# ringmod_osc.net
KiCad netlist of a schematic drawn in EAGLE
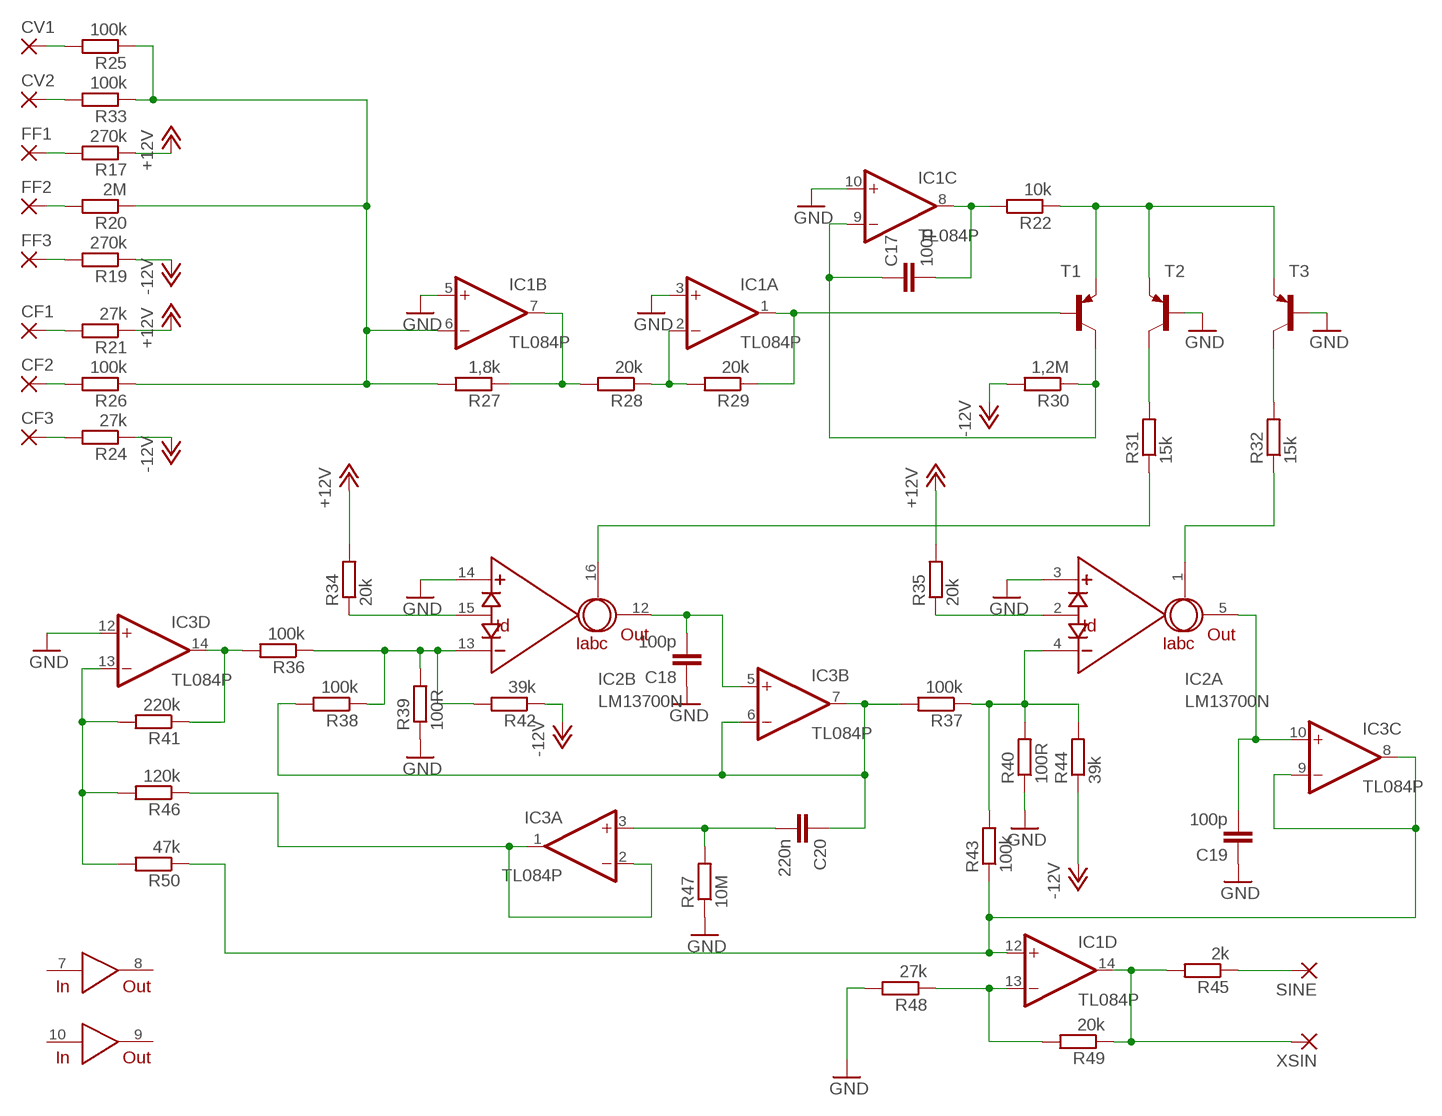
[diagram p0: schematic, sheet 1]
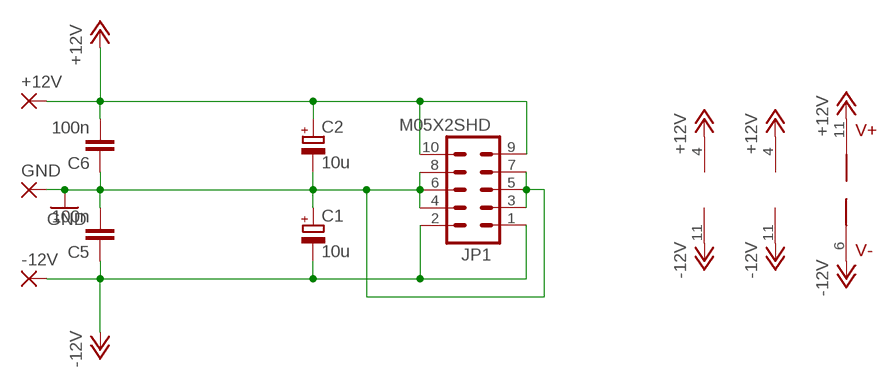
[diagram p1: schematic, sheet 2]

(export (version "E")
  (design (tool "Eeschema 10.0.6"))
  (components
    (comp (ref "+12V")
      (value "2,54/1,0")
      (footprint "eagle-import:2,54_1,0")
      (libsource (lib "eagle-import") (part "2,54/1,0"))
    )
    (comp (ref "-12V")
      (value "2,54/1,0")
      (footprint "eagle-import:2,54_1,0")
      (libsource (lib "eagle-import") (part "2,54/1,0"))
    )
    (comp (ref "C1")
      (value "10u")
      (footprint "eagle-import:E3,5-8")
      (libsource (lib "eagle-import") (part "CPOL-EUE3.5-8"))
    )
    (comp (ref "C2")
      (value "10u")
      (footprint "eagle-import:E3,5-8")
      (libsource (lib "eagle-import") (part "CPOL-EUE3.5-8"))
    )
    (comp (ref "C5")
      (value "100n")
      (footprint "eagle-import:C050-035X075")
      (libsource (lib "eagle-import") (part "C-EU050-035X075"))
    )
    (comp (ref "C6")
      (value "100n")
      (footprint "eagle-import:C050-035X075")
      (libsource (lib "eagle-import") (part "C-EU050-035X075"))
    )
    (comp (ref "GND")
      (value "2,54/1,0")
      (footprint "eagle-import:2,54_1,0")
      (libsource (lib "eagle-import") (part "2,54/1,0"))
    )
    (comp (ref "IC1")
      (value "TL084P")
      (footprint "eagle-import:DIL14")
      (libsource (lib "eagle-import") (part "TL084P"))
    )
    (comp (ref "IC2")
      (value "LM13700N")
      (footprint "eagle-import:DIL16")
      (libsource (lib "eagle-import") (part "LM13700N"))
    )
    (comp (ref "IC3")
      (value "TL084P")
      (footprint "eagle-import:DIL14")
      (libsource (lib "eagle-import") (part "TL084P"))
    )
    (comp (ref "JP1")
      (value "M05X2SHD")
      (footprint "eagle-import:2X5-SHROUDED")
      (libsource (lib "eagle-import") (part "M05X2SHD"))
    )
    (comp (ref "C17")
      (value "100p")
      (footprint "eagle-import:C050-035X075")
      (libsource (lib "eagle-import") (part "C-EU050-035X075"))
    )
    (comp (ref "C18")
      (value "100p")
      (footprint "eagle-import:C050-035X075")
      (libsource (lib "eagle-import") (part "C-EU050-035X075"))
    )
    (comp (ref "C19")
      (value "100p")
      (footprint "eagle-import:C050-035X075")
      (libsource (lib "eagle-import") (part "C-EU050-035X075"))
    )
    (comp (ref "C20")
      (value "220n")
      (footprint "eagle-import:C050-035X075")
      (libsource (lib "eagle-import") (part "C-EU050-035X075"))
    )
    (comp (ref "CF1")
      (value "2,54/1,0")
      (footprint "eagle-import:2,54_1,0")
      (libsource (lib "eagle-import") (part "2,54/1,0"))
    )
    (comp (ref "CF2")
      (value "2,54/1,0")
      (footprint "eagle-import:2,54_1,0")
      (libsource (lib "eagle-import") (part "2,54/1,0"))
    )
    (comp (ref "CF3")
      (value "2,54/1,0")
      (footprint "eagle-import:2,54_1,0")
      (libsource (lib "eagle-import") (part "2,54/1,0"))
    )
    (comp (ref "CV1")
      (value "2,54/1,0")
      (footprint "eagle-import:2,54_1,0")
      (libsource (lib "eagle-import") (part "2,54/1,0"))
    )
    (comp (ref "CV2")
      (value "2,54/1,0")
      (footprint "eagle-import:2,54_1,0")
      (libsource (lib "eagle-import") (part "2,54/1,0"))
    )
    (comp (ref "FF1")
      (value "2,54/1,0")
      (footprint "eagle-import:2,54_1,0")
      (libsource (lib "eagle-import") (part "2,54/1,0"))
    )
    (comp (ref "FF2")
      (value "2,54/1,0")
      (footprint "eagle-import:2,54_1,0")
      (libsource (lib "eagle-import") (part "2,54/1,0"))
    )
    (comp (ref "FF3")
      (value "2,54/1,0")
      (footprint "eagle-import:2,54_1,0")
      (libsource (lib "eagle-import") (part "2,54/1,0"))
    )
    (comp (ref "R17")
      (value "270k")
      (footprint "eagle-import:0309V")
      (libsource (lib "eagle-import") (part "R-EU_0309/V"))
    )
    (comp (ref "R19")
      (value "270k")
      (footprint "eagle-import:0309V")
      (libsource (lib "eagle-import") (part "R-EU_0309/V"))
    )
    (comp (ref "R20")
      (value "2M")
      (footprint "eagle-import:0309V")
      (libsource (lib "eagle-import") (part "R-EU_0309/V"))
    )
    (comp (ref "R21")
      (value "27k")
      (footprint "eagle-import:0309V")
      (libsource (lib "eagle-import") (part "R-EU_0309/V"))
    )
    (comp (ref "R22")
      (value "10k")
      (footprint "eagle-import:0309_10")
      (libsource (lib "eagle-import") (part "R-EU_0309/10"))
    )
    (comp (ref "R24")
      (value "27k")
      (footprint "eagle-import:0309V")
      (libsource (lib "eagle-import") (part "R-EU_0309/V"))
    )
    (comp (ref "R25")
      (value "100k")
      (footprint "eagle-import:0309V")
      (libsource (lib "eagle-import") (part "R-EU_0309/V"))
    )
    (comp (ref "R26")
      (value "100k")
      (footprint "eagle-import:0309V")
      (libsource (lib "eagle-import") (part "R-EU_0309/V"))
    )
    (comp (ref "R27")
      (value "1,8k")
      (footprint "eagle-import:0309_10")
      (libsource (lib "eagle-import") (part "R-EU_0309/10"))
    )
    (comp (ref "R28")
      (value "20k")
      (footprint "eagle-import:0309_10")
      (libsource (lib "eagle-import") (part "R-EU_0309/10"))
    )
    (comp (ref "R29")
      (value "20k")
      (footprint "eagle-import:0309_10")
      (libsource (lib "eagle-import") (part "R-EU_0309/10"))
    )
    (comp (ref "R30")
      (value "1,2M")
      (footprint "eagle-import:0309_10")
      (libsource (lib "eagle-import") (part "R-EU_0309/10"))
    )
    (comp (ref "R31")
      (value "15k")
      (footprint "eagle-import:0309_10")
      (libsource (lib "eagle-import") (part "R-EU_0309/10"))
    )
    (comp (ref "R32")
      (value "15k")
      (footprint "eagle-import:0309_10")
      (libsource (lib "eagle-import") (part "R-EU_0309/10"))
    )
    (comp (ref "R33")
      (value "100k")
      (footprint "eagle-import:0309V")
      (libsource (lib "eagle-import") (part "R-EU_0309/V"))
    )
    (comp (ref "R34")
      (value "20k")
      (footprint "eagle-import:0309_10")
      (libsource (lib "eagle-import") (part "R-EU_0309/10"))
    )
    (comp (ref "R35")
      (value "20k")
      (footprint "eagle-import:0309_10")
      (libsource (lib "eagle-import") (part "R-EU_0309/10"))
    )
    (comp (ref "R36")
      (value "100k")
      (footprint "eagle-import:0309_10")
      (libsource (lib "eagle-import") (part "R-EU_0309/10"))
    )
    (comp (ref "R37")
      (value "100k")
      (footprint "eagle-import:0309_10")
      (libsource (lib "eagle-import") (part "R-EU_0309/10"))
    )
    (comp (ref "R38")
      (value "100k")
      (footprint "eagle-import:0309_10")
      (libsource (lib "eagle-import") (part "R-EU_0309/10"))
    )
    (comp (ref "R39")
      (value "100R")
      (footprint "eagle-import:0309_10")
      (libsource (lib "eagle-import") (part "R-EU_0309/10"))
    )
    (comp (ref "R40")
      (value "100R")
      (footprint "eagle-import:0309_10")
      (libsource (lib "eagle-import") (part "R-EU_0309/10"))
    )
    (comp (ref "R41")
      (value "220k")
      (footprint "eagle-import:0309_10")
      (libsource (lib "eagle-import") (part "R-EU_0309/10"))
    )
    (comp (ref "R42")
      (value "39k")
      (footprint "eagle-import:0309_10")
      (libsource (lib "eagle-import") (part "R-EU_0309/10"))
    )
    (comp (ref "R43")
      (value "100k")
      (footprint "eagle-import:0309_10")
      (libsource (lib "eagle-import") (part "R-EU_0309/10"))
    )
    (comp (ref "R44")
      (value "39k")
      (footprint "eagle-import:0309_10")
      (libsource (lib "eagle-import") (part "R-EU_0309/10"))
    )
    (comp (ref "R45")
      (value "2k")
      (footprint "eagle-import:0309_10")
      (libsource (lib "eagle-import") (part "R-EU_0309/10"))
    )
    (comp (ref "R46")
      (value "120k")
      (footprint "eagle-import:0309_10")
      (libsource (lib "eagle-import") (part "R-EU_0309/10"))
    )
    (comp (ref "R47")
      (value "10M")
      (footprint "eagle-import:0309_10")
      (libsource (lib "eagle-import") (part "R-EU_0309/10"))
    )
    (comp (ref "R48")
      (value "27k")
      (footprint "eagle-import:0309_10")
      (libsource (lib "eagle-import") (part "R-EU_0309/10"))
    )
    (comp (ref "R49")
      (value "20k")
      (footprint "eagle-import:0309_10")
      (libsource (lib "eagle-import") (part "R-EU_0309/10"))
    )
    (comp (ref "R50")
      (value "47k")
      (footprint "eagle-import:0309_10")
      (libsource (lib "eagle-import") (part "R-EU_0309/10"))
    )
    (comp (ref "SINE")
      (value "2,54/1,0")
      (footprint "eagle-import:2,54_1,0")
      (libsource (lib "eagle-import") (part "2,54/1,0"))
    )
    (comp (ref "T1")
      (value "2N3906-PNP-TO92-EBC")
      (footprint "eagle-import:TO92-EBC")
      (libsource (lib "eagle-import") (part "-PNP-TO92-EBC2N3906"))
    )
    (comp (ref "T2")
      (value "2N3906-PNP-TO92-EBC")
      (footprint "eagle-import:TO92-EBC")
      (libsource (lib "eagle-import") (part "-PNP-TO92-EBC2N3906"))
    )
    (comp (ref "T3")
      (value "2N3906-PNP-TO92-EBC")
      (footprint "eagle-import:TO92-EBC")
      (libsource (lib "eagle-import") (part "-PNP-TO92-EBC2N3906"))
    )
    (comp (ref "XSIN")
      (value "2,54/1,0")
      (footprint "eagle-import:2,54_1,0")
      (libsource (lib "eagle-import") (part "2,54/1,0"))
    )
  )
  (nets
    (net (code "1") (name "+12V") (class "Default")
      (node (ref "+12V") (pin "1") (pinfunction "P_1") (pintype "passive"))
      (node (ref "C2") (pin "+") (pinfunction "+_+") (pintype "passive"))
      (node (ref "C6") (pin "2") (pinfunction "2_2") (pintype "passive"))
      (node (ref "IC1") (pin "4") (pinfunction "V+_4") (pintype "power_in"))
      (node (ref "IC2") (pin "11") (pinfunction "V+_11") (pintype "bidirectional"))
      (node (ref "IC3") (pin "4") (pinfunction "V+_4") (pintype "power_in"))
      (node (ref "JP1") (pin "10") (pinfunction "10_10") (pintype "passive"))
      (node (ref "JP1") (pin "9") (pinfunction "9_9") (pintype "passive"))
      (node (ref "R17") (pin "1") (pinfunction "1_1") (pintype "passive"))
      (node (ref "R21") (pin "1") (pinfunction "1_1") (pintype "passive"))
      (node (ref "R34") (pin "2") (pinfunction "2_2") (pintype "passive"))
      (node (ref "R35") (pin "2") (pinfunction "2_2") (pintype "passive"))
    )
    (net (code "2") (name "-12V") (class "Default")
      (node (ref "-12V") (pin "1") (pinfunction "P_1") (pintype "passive"))
      (node (ref "C1") (pin "-") (pinfunction "-_-") (pintype "passive"))
      (node (ref "C5") (pin "1") (pinfunction "1_1") (pintype "passive"))
      (node (ref "IC1") (pin "11") (pinfunction "V-_11") (pintype "power_in"))
      (node (ref "IC2") (pin "6") (pinfunction "V-_6") (pintype "bidirectional"))
      (node (ref "IC3") (pin "11") (pinfunction "V-_11") (pintype "power_in"))
      (node (ref "JP1") (pin "1") (pinfunction "1_1") (pintype "passive"))
      (node (ref "JP1") (pin "2") (pinfunction "2_2") (pintype "passive"))
      (node (ref "R19") (pin "1") (pinfunction "1_1") (pintype "passive"))
      (node (ref "R24") (pin "1") (pinfunction "1_1") (pintype "passive"))
      (node (ref "R30") (pin "2") (pinfunction "2_2") (pintype "passive"))
      (node (ref "R42") (pin "1") (pinfunction "1_1") (pintype "passive"))
      (node (ref "R44") (pin "1") (pinfunction "1_1") (pintype "passive"))
    )
    (net (code "3") (name "GND") (class "Default")
      (node (ref "C1") (pin "+") (pinfunction "+_+") (pintype "passive"))
      (node (ref "C18") (pin "1") (pinfunction "1_1") (pintype "passive"))
      (node (ref "C19") (pin "1") (pinfunction "1_1") (pintype "passive"))
      (node (ref "C2") (pin "-") (pinfunction "-_-") (pintype "passive"))
      (node (ref "C5") (pin "2") (pinfunction "2_2") (pintype "passive"))
      (node (ref "C6") (pin "1") (pinfunction "1_1") (pintype "passive"))
      (node (ref "GND") (pin "1") (pinfunction "P_1") (pintype "passive"))
      (node (ref "IC1") (pin "10") (pinfunction "+IN_10") (pintype "input"))
      (node (ref "IC1") (pin "3") (pinfunction "+IN_3") (pintype "input"))
      (node (ref "IC1") (pin "5") (pinfunction "+IN_5") (pintype "input"))
      (node (ref "IC2") (pin "14") (pinfunction "+IN_14") (pintype "bidirectional"))
      (node (ref "IC2") (pin "3") (pinfunction "+IN_3") (pintype "bidirectional"))
      (node (ref "IC3") (pin "12") (pinfunction "+IN_12") (pintype "input"))
      (node (ref "JP1") (pin "3") (pinfunction "3_3") (pintype "passive"))
      (node (ref "JP1") (pin "4") (pinfunction "4_4") (pintype "passive"))
      (node (ref "JP1") (pin "5") (pinfunction "5_5") (pintype "passive"))
      (node (ref "JP1") (pin "6") (pinfunction "6_6") (pintype "passive"))
      (node (ref "JP1") (pin "7") (pinfunction "7_7") (pintype "passive"))
      (node (ref "JP1") (pin "8") (pinfunction "8_8") (pintype "passive"))
      (node (ref "R39") (pin "1") (pinfunction "1_1") (pintype "passive"))
      (node (ref "R40") (pin "1") (pinfunction "1_1") (pintype "passive"))
      (node (ref "R47") (pin "1") (pinfunction "1_1") (pintype "passive"))
      (node (ref "R48") (pin "2") (pinfunction "2_2") (pintype "passive"))
      (node (ref "T2") (pin "B") (pinfunction "B_B") (pintype "passive"))
      (node (ref "T3") (pin "B") (pinfunction "B_B") (pintype "passive"))
    )
    (net (code "4") (name "Net-(CF1-P)") (class "Default")
      (node (ref "CF1") (pin "1") (pinfunction "P_1") (pintype "passive"))
      (node (ref "R21") (pin "2") (pinfunction "2_2") (pintype "passive"))
    )
    (net (code "5") (name "Net-(CF2-P)") (class "Default")
      (node (ref "CF2") (pin "1") (pinfunction "P_1") (pintype "passive"))
      (node (ref "R26") (pin "2") (pinfunction "2_2") (pintype "passive"))
    )
    (net (code "6") (name "Net-(CF3-P)") (class "Default")
      (node (ref "CF3") (pin "1") (pinfunction "P_1") (pintype "passive"))
      (node (ref "R24") (pin "2") (pinfunction "2_2") (pintype "passive"))
    )
    (net (code "7") (name "Net-(CV1-P)") (class "Default")
      (node (ref "CV1") (pin "1") (pinfunction "P_1") (pintype "passive"))
      (node (ref "R25") (pin "2") (pinfunction "2_2") (pintype "passive"))
    )
    (net (code "8") (name "Net-(CV2-P)") (class "Default")
      (node (ref "CV2") (pin "1") (pinfunction "P_1") (pintype "passive"))
      (node (ref "R33") (pin "2") (pinfunction "2_2") (pintype "passive"))
    )
    (net (code "9") (name "Net-(FF1-P)") (class "Default")
      (node (ref "FF1") (pin "1") (pinfunction "P_1") (pintype "passive"))
      (node (ref "R17") (pin "2") (pinfunction "2_2") (pintype "passive"))
    )
    (net (code "10") (name "Net-(FF2-P)") (class "Default")
      (node (ref "FF2") (pin "1") (pinfunction "P_1") (pintype "passive"))
      (node (ref "R20") (pin "2") (pinfunction "2_2") (pintype "passive"))
    )
    (net (code "11") (name "Net-(FF3-P)") (class "Default")
      (node (ref "FF3") (pin "1") (pinfunction "P_1") (pintype "passive"))
      (node (ref "R19") (pin "2") (pinfunction "2_2") (pintype "passive"))
    )
    (net (code "12") (name "Net-(IC1A--IN)") (class "Default")
      (node (ref "IC1") (pin "2") (pinfunction "-IN_2") (pintype "input"))
      (node (ref "R28") (pin "1") (pinfunction "1_1") (pintype "passive"))
      (node (ref "R29") (pin "2") (pinfunction "2_2") (pintype "passive"))
    )
    (net (code "13") (name "Net-(IC1A-OUT)") (class "Default")
      (node (ref "IC1") (pin "1") (pinfunction "OUT_1") (pintype "output"))
      (node (ref "R29") (pin "1") (pinfunction "1_1") (pintype "passive"))
      (node (ref "T1") (pin "B") (pinfunction "B_B") (pintype "passive"))
    )
    (net (code "14") (name "Net-(IC1B--IN)") (class "Default")
      (node (ref "IC1") (pin "6") (pinfunction "-IN_6") (pintype "input"))
      (node (ref "R20") (pin "1") (pinfunction "1_1") (pintype "passive"))
      (node (ref "R25") (pin "1") (pinfunction "1_1") (pintype "passive"))
      (node (ref "R26") (pin "1") (pinfunction "1_1") (pintype "passive"))
      (node (ref "R27") (pin "2") (pinfunction "2_2") (pintype "passive"))
      (node (ref "R33") (pin "1") (pinfunction "1_1") (pintype "passive"))
    )
    (net (code "15") (name "Net-(IC1B-OUT)") (class "Default")
      (node (ref "IC1") (pin "7") (pinfunction "OUT_7") (pintype "output"))
      (node (ref "R27") (pin "1") (pinfunction "1_1") (pintype "passive"))
      (node (ref "R28") (pin "2") (pinfunction "2_2") (pintype "passive"))
    )
    (net (code "16") (name "Net-(IC1C--IN)") (class "Default")
      (node (ref "C17") (pin "1") (pinfunction "1_1") (pintype "passive"))
      (node (ref "IC1") (pin "9") (pinfunction "-IN_9") (pintype "input"))
      (node (ref "R30") (pin "1") (pinfunction "1_1") (pintype "passive"))
      (node (ref "T1") (pin "C") (pinfunction "C_C") (pintype "passive"))
    )
    (net (code "17") (name "Net-(IC1C-OUT)") (class "Default")
      (node (ref "C17") (pin "2") (pinfunction "2_2") (pintype "passive"))
      (node (ref "IC1") (pin "8") (pinfunction "OUT_8") (pintype "output"))
      (node (ref "R22") (pin "2") (pinfunction "2_2") (pintype "passive"))
    )
    (net (code "18") (name "Net-(IC1D-+IN)") (class "Default")
      (node (ref "IC1") (pin "12") (pinfunction "+IN_12") (pintype "input"))
      (node (ref "IC3") (pin "8") (pinfunction "OUT_8") (pintype "output"))
      (node (ref "IC3") (pin "9") (pinfunction "-IN_9") (pintype "input"))
      (node (ref "R43") (pin "1") (pinfunction "1_1") (pintype "passive"))
      (node (ref "R50") (pin "1") (pinfunction "1_1") (pintype "passive"))
    )
    (net (code "19") (name "Net-(IC1D--IN)") (class "Default")
      (node (ref "IC1") (pin "13") (pinfunction "-IN_13") (pintype "input"))
      (node (ref "R48") (pin "1") (pinfunction "1_1") (pintype "passive"))
      (node (ref "R49") (pin "2") (pinfunction "2_2") (pintype "passive"))
    )
    (net (code "20") (name "Net-(IC1D-OUT)") (class "Default")
      (node (ref "IC1") (pin "14") (pinfunction "OUT_14") (pintype "output"))
      (node (ref "R45") (pin "2") (pinfunction "2_2") (pintype "passive"))
      (node (ref "R49") (pin "1") (pinfunction "1_1") (pintype "passive"))
      (node (ref "XSIN") (pin "1") (pinfunction "P_1") (pintype "passive"))
    )
    (net (code "21") (name "Net-(IC2A--IN)") (class "Default")
      (node (ref "IC2") (pin "4") (pinfunction "-IN_4") (pintype "bidirectional"))
      (node (ref "R37") (pin "1") (pinfunction "1_1") (pintype "passive"))
      (node (ref "R40") (pin "2") (pinfunction "2_2") (pintype "passive"))
      (node (ref "R43") (pin "2") (pinfunction "2_2") (pintype "passive"))
      (node (ref "R44") (pin "2") (pinfunction "2_2") (pintype "passive"))
    )
    (net (code "22") (name "Net-(IC2A-IABC)") (class "Default")
      (node (ref "IC2") (pin "1") (pinfunction "IABC_1") (pintype "bidirectional"))
      (node (ref "R32") (pin "1") (pinfunction "1_1") (pintype "passive"))
    )
    (net (code "23") (name "Net-(IC2A-ID)") (class "Default")
      (node (ref "IC2") (pin "2") (pinfunction "ID_2") (pintype "bidirectional"))
      (node (ref "R35") (pin "1") (pinfunction "1_1") (pintype "passive"))
    )
    (net (code "24") (name "Net-(IC2A-OUT)") (class "Default")
      (node (ref "C19") (pin "2") (pinfunction "2_2") (pintype "passive"))
      (node (ref "IC2") (pin "5") (pinfunction "OUT_5") (pintype "bidirectional"))
      (node (ref "IC3") (pin "10") (pinfunction "+IN_10") (pintype "input"))
    )
    (net (code "25") (name "Net-(IC2B--IN)") (class "Default")
      (node (ref "IC2") (pin "13") (pinfunction "-IN_13") (pintype "bidirectional"))
      (node (ref "R36") (pin "1") (pinfunction "1_1") (pintype "passive"))
      (node (ref "R38") (pin "1") (pinfunction "1_1") (pintype "passive"))
      (node (ref "R39") (pin "2") (pinfunction "2_2") (pintype "passive"))
      (node (ref "R42") (pin "2") (pinfunction "2_2") (pintype "passive"))
    )
    (net (code "26") (name "Net-(IC2B-IABC)") (class "Default")
      (node (ref "IC2") (pin "16") (pinfunction "IABC_16") (pintype "bidirectional"))
      (node (ref "R31") (pin "1") (pinfunction "1_1") (pintype "passive"))
    )
    (net (code "27") (name "Net-(IC2B-ID)") (class "Default")
      (node (ref "IC2") (pin "15") (pinfunction "ID_15") (pintype "bidirectional"))
      (node (ref "R34") (pin "1") (pinfunction "1_1") (pintype "passive"))
    )
    (net (code "28") (name "Net-(IC2B-OUT)") (class "Default")
      (node (ref "C18") (pin "2") (pinfunction "2_2") (pintype "passive"))
      (node (ref "IC2") (pin "12") (pinfunction "OUT_12") (pintype "bidirectional"))
      (node (ref "IC3") (pin "5") (pinfunction "+IN_5") (pintype "input"))
    )
    (net (code "29") (name "Net-(IC3A-+IN)") (class "Default")
      (node (ref "C20") (pin "2") (pinfunction "2_2") (pintype "passive"))
      (node (ref "IC3") (pin "3") (pinfunction "+IN_3") (pintype "input"))
      (node (ref "R47") (pin "2") (pinfunction "2_2") (pintype "passive"))
    )
    (net (code "30") (name "Net-(IC3A--IN)") (class "Default")
      (node (ref "IC3") (pin "1") (pinfunction "OUT_1") (pintype "output"))
      (node (ref "IC3") (pin "2") (pinfunction "-IN_2") (pintype "input"))
      (node (ref "R46") (pin "1") (pinfunction "1_1") (pintype "passive"))
    )
    (net (code "31") (name "Net-(IC3B--IN)") (class "Default")
      (node (ref "C20") (pin "1") (pinfunction "1_1") (pintype "passive"))
      (node (ref "IC3") (pin "6") (pinfunction "-IN_6") (pintype "input"))
      (node (ref "IC3") (pin "7") (pinfunction "OUT_7") (pintype "output"))
      (node (ref "R37") (pin "2") (pinfunction "2_2") (pintype "passive"))
      (node (ref "R38") (pin "2") (pinfunction "2_2") (pintype "passive"))
    )
    (net (code "32") (name "Net-(IC3D--IN)") (class "Default")
      (node (ref "IC3") (pin "13") (pinfunction "-IN_13") (pintype "input"))
      (node (ref "R41") (pin "2") (pinfunction "2_2") (pintype "passive"))
      (node (ref "R46") (pin "2") (pinfunction "2_2") (pintype "passive"))
      (node (ref "R50") (pin "2") (pinfunction "2_2") (pintype "passive"))
    )
    (net (code "33") (name "Net-(IC3D-OUT)") (class "Default")
      (node (ref "IC3") (pin "14") (pinfunction "OUT_14") (pintype "output"))
      (node (ref "R36") (pin "2") (pinfunction "2_2") (pintype "passive"))
      (node (ref "R41") (pin "1") (pinfunction "1_1") (pintype "passive"))
    )
    (net (code "34") (name "Net-(R22-Pad1)") (class "Default")
      (node (ref "R22") (pin "1") (pinfunction "1_1") (pintype "passive"))
      (node (ref "T1") (pin "E") (pinfunction "E_E") (pintype "passive"))
      (node (ref "T2") (pin "E") (pinfunction "E_E") (pintype "passive"))
      (node (ref "T3") (pin "E") (pinfunction "E_E") (pintype "passive"))
    )
    (net (code "35") (name "Net-(R31-Pad2)") (class "Default")
      (node (ref "R31") (pin "2") (pinfunction "2_2") (pintype "passive"))
      (node (ref "T2") (pin "C") (pinfunction "C_C") (pintype "passive"))
    )
    (net (code "36") (name "Net-(R32-Pad2)") (class "Default")
      (node (ref "R32") (pin "2") (pinfunction "2_2") (pintype "passive"))
      (node (ref "T3") (pin "C") (pinfunction "C_C") (pintype "passive"))
    )
    (net (code "37") (name "Net-(SINE-P)") (class "Default")
      (node (ref "R45") (pin "1") (pinfunction "1_1") (pintype "passive"))
      (node (ref "SINE") (pin "1") (pinfunction "P_1") (pintype "passive"))
    )
    (net (code "38") (name "unconnected-(IC2C-IN-Pad7)") (class "Default")
      (node (ref "IC2") (pin "7") (pinfunction "IN_7") (pintype "bidirectional"))
    )
    (net (code "39") (name "unconnected-(IC2C-OUT-Pad8)") (class "Default")
      (node (ref "IC2") (pin "8") (pinfunction "OUT_8") (pintype "bidirectional"))
    )
    (net (code "40") (name "unconnected-(IC2D-IN-Pad10)") (class "Default")
      (node (ref "IC2") (pin "10") (pinfunction "IN_10") (pintype "bidirectional"))
    )
    (net (code "41") (name "unconnected-(IC2D-OUT-Pad9)") (class "Default")
      (node (ref "IC2") (pin "9") (pinfunction "OUT_9") (pintype "bidirectional"))
    )
  )
)
